# bobis.net
KiCad netlist of a schematic drawn in EAGLE
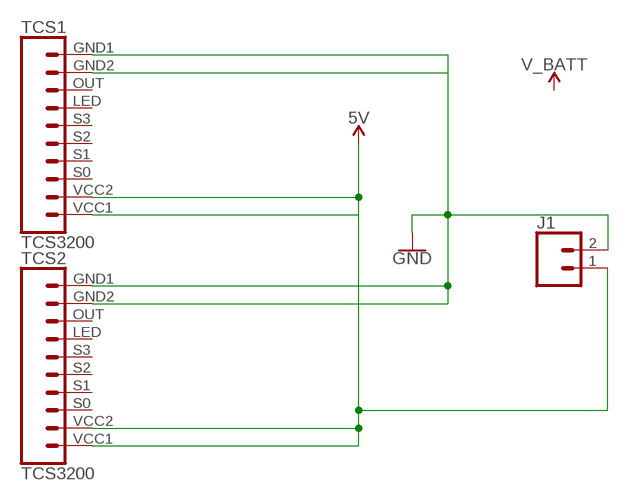
[diagram p0: schematic, sheet 1]

(export (version "E")
  (design (tool "Eeschema 10.0.6"))
  (components
    (comp (ref "J1")
      (value "CONN_02")
      (footprint "eagle-import:1X02")
      (libsource (lib "eagle-import") (part "CONN_02"))
    )
    (comp (ref "TCS1")
      (value "TCS3200")
      (footprint "eagle-import:TCS3200")
      (libsource (lib "eagle-import") (part "TCS3200"))
    )
    (comp (ref "TCS2")
      (value "TCS3200")
      (footprint "eagle-import:TCS3200")
      (libsource (lib "eagle-import") (part "TCS3200"))
    )
  )
  (nets
    (net (code "1") (name "5V") (class "Default")
      (node (ref "J1") (pin "1") (pinfunction "1_1") (pintype "passive"))
      (node (ref "TCS1") (pin "VCC1") (pinfunction "VCC1_VCC1") (pintype "passive"))
      (node (ref "TCS1") (pin "VCC2") (pinfunction "VCC2_VCC2") (pintype "passive"))
      (node (ref "TCS2") (pin "VCC1") (pinfunction "VCC1_VCC1") (pintype "passive"))
      (node (ref "TCS2") (pin "VCC2") (pinfunction "VCC2_VCC2") (pintype "passive"))
    )
    (net (code "2") (name "GND") (class "Default")
      (node (ref "J1") (pin "2") (pinfunction "2_2") (pintype "passive"))
      (node (ref "TCS1") (pin "GND1") (pinfunction "GND1_GND1") (pintype "passive"))
      (node (ref "TCS1") (pin "GND2") (pinfunction "GND2_GND2") (pintype "passive"))
      (node (ref "TCS2") (pin "GND1") (pinfunction "GND1_GND1") (pintype "passive"))
      (node (ref "TCS2") (pin "GND2") (pinfunction "GND2_GND2") (pintype "passive"))
    )
    (net (code "4") (name "unconnected-(TCS1-PadLED)") (class "Default")
      (node (ref "TCS1") (pin "LED") (pinfunction "LED_LED") (pintype "passive"))
    )
    (net (code "5") (name "unconnected-(TCS1-PadOUT)") (class "Default")
      (node (ref "TCS1") (pin "OUT") (pinfunction "OUT_OUT") (pintype "passive"))
    )
    (net (code "6") (name "unconnected-(TCS1-PadS0)") (class "Default")
      (node (ref "TCS1") (pin "S0") (pinfunction "S0_S0") (pintype "passive"))
    )
    (net (code "7") (name "unconnected-(TCS1-PadS1)") (class "Default")
      (node (ref "TCS1") (pin "S1") (pinfunction "S1_S1") (pintype "passive"))
    )
    (net (code "8") (name "unconnected-(TCS1-PadS2)") (class "Default")
      (node (ref "TCS1") (pin "S2") (pinfunction "S2_S2") (pintype "passive"))
    )
    (net (code "9") (name "unconnected-(TCS1-PadS3)") (class "Default")
      (node (ref "TCS1") (pin "S3") (pinfunction "S3_S3") (pintype "passive"))
    )
    (net (code "10") (name "unconnected-(TCS2-PadLED)") (class "Default")
      (node (ref "TCS2") (pin "LED") (pinfunction "LED_LED") (pintype "passive"))
    )
    (net (code "11") (name "unconnected-(TCS2-PadOUT)") (class "Default")
      (node (ref "TCS2") (pin "OUT") (pinfunction "OUT_OUT") (pintype "passive"))
    )
    (net (code "12") (name "unconnected-(TCS2-PadS0)") (class "Default")
      (node (ref "TCS2") (pin "S0") (pinfunction "S0_S0") (pintype "passive"))
    )
    (net (code "13") (name "unconnected-(TCS2-PadS1)") (class "Default")
      (node (ref "TCS2") (pin "S1") (pinfunction "S1_S1") (pintype "passive"))
    )
    (net (code "14") (name "unconnected-(TCS2-PadS2)") (class "Default")
      (node (ref "TCS2") (pin "S2") (pinfunction "S2_S2") (pintype "passive"))
    )
    (net (code "15") (name "unconnected-(TCS2-PadS3)") (class "Default")
      (node (ref "TCS2") (pin "S3") (pinfunction "S3_S3") (pintype "passive"))
    )
  )
)
